# LED_Matrix_3_1.net
KiCad netlist of a schematic drawn in EAGLE
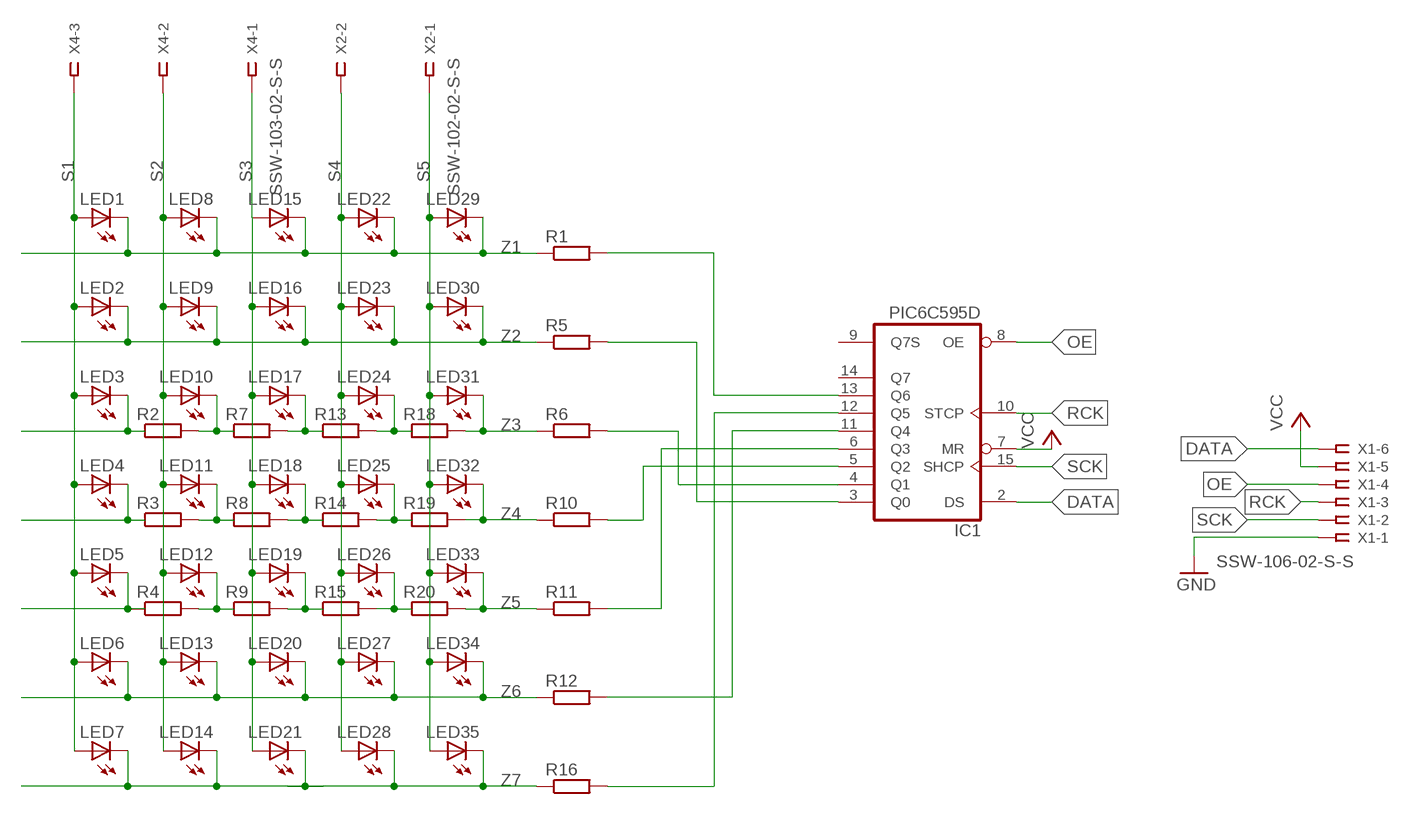
[diagram p0: schematic, sheet 1]

(export (version "E")
  (design (tool "Eeschema 10.0.6"))
  (components
    (comp (ref "IC1")
      (value "PIC6C595D")
      (footprint "eagle-import:SO16")
      (libsource (lib "eagle-import") (part "PIC6C595D"))
    )
    (comp (ref "LED1")
      (value "LEDCHIP-LED0603")
      (footprint "eagle-import:CHIP-LED0603")
      (libsource (lib "eagle-import") (part "LEDCHIP-LED0603"))
    )
    (comp (ref "LED2")
      (value "LEDCHIP-LED0603")
      (footprint "eagle-import:CHIP-LED0603")
      (libsource (lib "eagle-import") (part "LEDCHIP-LED0603"))
    )
    (comp (ref "LED3")
      (value "LEDCHIP-LED0603")
      (footprint "eagle-import:CHIP-LED0603")
      (libsource (lib "eagle-import") (part "LEDCHIP-LED0603"))
    )
    (comp (ref "LED4")
      (value "LEDCHIP-LED0603")
      (footprint "eagle-import:CHIP-LED0603")
      (libsource (lib "eagle-import") (part "LEDCHIP-LED0603"))
    )
    (comp (ref "LED5")
      (value "LEDCHIP-LED0603")
      (footprint "eagle-import:CHIP-LED0603")
      (libsource (lib "eagle-import") (part "LEDCHIP-LED0603"))
    )
    (comp (ref "LED6")
      (value "LEDCHIP-LED0603")
      (footprint "eagle-import:CHIP-LED0603")
      (libsource (lib "eagle-import") (part "LEDCHIP-LED0603"))
    )
    (comp (ref "LED7")
      (value "LEDCHIP-LED0603")
      (footprint "eagle-import:CHIP-LED0603")
      (libsource (lib "eagle-import") (part "LEDCHIP-LED0603"))
    )
    (comp (ref "LED8")
      (value "LEDCHIP-LED0603")
      (footprint "eagle-import:CHIP-LED0603")
      (libsource (lib "eagle-import") (part "LEDCHIP-LED0603"))
    )
    (comp (ref "LED9")
      (value "LEDCHIP-LED0603")
      (footprint "eagle-import:CHIP-LED0603")
      (libsource (lib "eagle-import") (part "LEDCHIP-LED0603"))
    )
    (comp (ref "LED10")
      (value "LEDCHIP-LED0603")
      (footprint "eagle-import:CHIP-LED0603")
      (libsource (lib "eagle-import") (part "LEDCHIP-LED0603"))
    )
    (comp (ref "LED11")
      (value "LEDCHIP-LED0603")
      (footprint "eagle-import:CHIP-LED0603")
      (libsource (lib "eagle-import") (part "LEDCHIP-LED0603"))
    )
    (comp (ref "LED12")
      (value "LEDCHIP-LED0603")
      (footprint "eagle-import:CHIP-LED0603")
      (libsource (lib "eagle-import") (part "LEDCHIP-LED0603"))
    )
    (comp (ref "LED13")
      (value "LEDCHIP-LED0603")
      (footprint "eagle-import:CHIP-LED0603")
      (libsource (lib "eagle-import") (part "LEDCHIP-LED0603"))
    )
    (comp (ref "LED14")
      (value "LEDCHIP-LED0603")
      (footprint "eagle-import:CHIP-LED0603")
      (libsource (lib "eagle-import") (part "LEDCHIP-LED0603"))
    )
    (comp (ref "LED15")
      (value "LEDCHIP-LED0603")
      (footprint "eagle-import:CHIP-LED0603")
      (libsource (lib "eagle-import") (part "LEDCHIP-LED0603"))
    )
    (comp (ref "LED16")
      (value "LEDCHIP-LED0603")
      (footprint "eagle-import:CHIP-LED0603")
      (libsource (lib "eagle-import") (part "LEDCHIP-LED0603"))
    )
    (comp (ref "LED17")
      (value "LEDCHIP-LED0603")
      (footprint "eagle-import:CHIP-LED0603")
      (libsource (lib "eagle-import") (part "LEDCHIP-LED0603"))
    )
    (comp (ref "LED18")
      (value "LEDCHIP-LED0603")
      (footprint "eagle-import:CHIP-LED0603")
      (libsource (lib "eagle-import") (part "LEDCHIP-LED0603"))
    )
    (comp (ref "LED19")
      (value "LEDCHIP-LED0603")
      (footprint "eagle-import:CHIP-LED0603")
      (libsource (lib "eagle-import") (part "LEDCHIP-LED0603"))
    )
    (comp (ref "LED20")
      (value "LEDCHIP-LED0603")
      (footprint "eagle-import:CHIP-LED0603")
      (libsource (lib "eagle-import") (part "LEDCHIP-LED0603"))
    )
    (comp (ref "LED21")
      (value "LEDCHIP-LED0603")
      (footprint "eagle-import:CHIP-LED0603")
      (libsource (lib "eagle-import") (part "LEDCHIP-LED0603"))
    )
    (comp (ref "LED22")
      (value "LEDCHIP-LED0603")
      (footprint "eagle-import:CHIP-LED0603")
      (libsource (lib "eagle-import") (part "LEDCHIP-LED0603"))
    )
    (comp (ref "LED23")
      (value "LEDCHIP-LED0603")
      (footprint "eagle-import:CHIP-LED0603")
      (libsource (lib "eagle-import") (part "LEDCHIP-LED0603"))
    )
    (comp (ref "LED24")
      (value "LEDCHIP-LED0603")
      (footprint "eagle-import:CHIP-LED0603")
      (libsource (lib "eagle-import") (part "LEDCHIP-LED0603"))
    )
    (comp (ref "LED25")
      (value "LEDCHIP-LED0603")
      (footprint "eagle-import:CHIP-LED0603")
      (libsource (lib "eagle-import") (part "LEDCHIP-LED0603"))
    )
    (comp (ref "LED26")
      (value "LEDCHIP-LED0603")
      (footprint "eagle-import:CHIP-LED0603")
      (libsource (lib "eagle-import") (part "LEDCHIP-LED0603"))
    )
    (comp (ref "LED27")
      (value "LEDCHIP-LED0603")
      (footprint "eagle-import:CHIP-LED0603")
      (libsource (lib "eagle-import") (part "LEDCHIP-LED0603"))
    )
    (comp (ref "LED28")
      (value "LEDCHIP-LED0603")
      (footprint "eagle-import:CHIP-LED0603")
      (libsource (lib "eagle-import") (part "LEDCHIP-LED0603"))
    )
    (comp (ref "LED29")
      (value "LEDCHIP-LED0603")
      (footprint "eagle-import:CHIP-LED0603")
      (libsource (lib "eagle-import") (part "LEDCHIP-LED0603"))
    )
    (comp (ref "LED30")
      (value "LEDCHIP-LED0603")
      (footprint "eagle-import:CHIP-LED0603")
      (libsource (lib "eagle-import") (part "LEDCHIP-LED0603"))
    )
    (comp (ref "LED31")
      (value "LEDCHIP-LED0603")
      (footprint "eagle-import:CHIP-LED0603")
      (libsource (lib "eagle-import") (part "LEDCHIP-LED0603"))
    )
    (comp (ref "LED32")
      (value "LEDCHIP-LED0603")
      (footprint "eagle-import:CHIP-LED0603")
      (libsource (lib "eagle-import") (part "LEDCHIP-LED0603"))
    )
    (comp (ref "LED33")
      (value "LEDCHIP-LED0603")
      (footprint "eagle-import:CHIP-LED0603")
      (libsource (lib "eagle-import") (part "LEDCHIP-LED0603"))
    )
    (comp (ref "LED34")
      (value "LEDCHIP-LED0603")
      (footprint "eagle-import:CHIP-LED0603")
      (libsource (lib "eagle-import") (part "LEDCHIP-LED0603"))
    )
    (comp (ref "LED35")
      (value "LEDCHIP-LED0603")
      (footprint "eagle-import:CHIP-LED0603")
      (libsource (lib "eagle-import") (part "LEDCHIP-LED0603"))
    )
    (comp (ref "R1")
      (value "R-EU_R0603")
      (footprint "eagle-import:R0603")
      (libsource (lib "eagle-import") (part "resistor_R-EU_R0603"))
    )
    (comp (ref "R2")
      (value "R-EU_R0603")
      (footprint "eagle-import:R0603")
      (libsource (lib "eagle-import") (part "R-EU_R0603"))
    )
    (comp (ref "R3")
      (value "R-EU_R0603")
      (footprint "eagle-import:R0603")
      (libsource (lib "eagle-import") (part "R-EU_R0603"))
    )
    (comp (ref "R4")
      (value "R-EU_R0603")
      (footprint "eagle-import:R0603")
      (libsource (lib "eagle-import") (part "R-EU_R0603"))
    )
    (comp (ref "R5")
      (value "R-EU_R0603")
      (footprint "eagle-import:R0603")
      (libsource (lib "eagle-import") (part "resistor_R-EU_R0603"))
    )
    (comp (ref "R6")
      (value "R-EU_R0603")
      (footprint "eagle-import:R0603")
      (libsource (lib "eagle-import") (part "resistor_R-EU_R0603"))
    )
    (comp (ref "R7")
      (value "R-EU_R0603")
      (footprint "eagle-import:R0603")
      (libsource (lib "eagle-import") (part "R-EU_R0603"))
    )
    (comp (ref "R8")
      (value "R-EU_R0603")
      (footprint "eagle-import:R0603")
      (libsource (lib "eagle-import") (part "R-EU_R0603"))
    )
    (comp (ref "R9")
      (value "R-EU_R0603")
      (footprint "eagle-import:R0603")
      (libsource (lib "eagle-import") (part "R-EU_R0603"))
    )
    (comp (ref "R10")
      (value "R-EU_R0603")
      (footprint "eagle-import:R0603")
      (libsource (lib "eagle-import") (part "resistor_R-EU_R0603"))
    )
    (comp (ref "R11")
      (value "R-EU_R0603")
      (footprint "eagle-import:R0603")
      (libsource (lib "eagle-import") (part "resistor_R-EU_R0603"))
    )
    (comp (ref "R12")
      (value "R-EU_R0603")
      (footprint "eagle-import:R0603")
      (libsource (lib "eagle-import") (part "resistor_R-EU_R0603"))
    )
    (comp (ref "R13")
      (value "R-EU_R0603")
      (footprint "eagle-import:R0603")
      (libsource (lib "eagle-import") (part "R-EU_R0603"))
    )
    (comp (ref "R14")
      (value "R-EU_R0603")
      (footprint "eagle-import:R0603")
      (libsource (lib "eagle-import") (part "R-EU_R0603"))
    )
    (comp (ref "R15")
      (value "R-EU_R0603")
      (footprint "eagle-import:R0603")
      (libsource (lib "eagle-import") (part "R-EU_R0603"))
    )
    (comp (ref "R16")
      (value "R-EU_R0603")
      (footprint "eagle-import:R0603")
      (libsource (lib "eagle-import") (part "resistor_R-EU_R0603"))
    )
    (comp (ref "R18")
      (value "R-EU_R0603")
      (footprint "eagle-import:R0603")
      (libsource (lib "eagle-import") (part "R-EU_R0603"))
    )
    (comp (ref "R19")
      (value "R-EU_R0603")
      (footprint "eagle-import:R0603")
      (libsource (lib "eagle-import") (part "R-EU_R0603"))
    )
    (comp (ref "R20")
      (value "R-EU_R0603")
      (footprint "eagle-import:R0603")
      (libsource (lib "eagle-import") (part "R-EU_R0603"))
    )
    (comp (ref "X1")
      (value "SSW-106-02-S-S")
      (footprint "eagle-import:SSW-106-02-S-S")
      (libsource (lib "eagle-import") (part "SSW-106-02-S-S"))
    )
    (comp (ref "X2")
      (value "SSW-102-02-S-S")
      (footprint "eagle-import:SSW-102-02-S-S")
      (libsource (lib "eagle-import") (part "SSW-102-02-S-S"))
    )
    (comp (ref "X4")
      (value "SSW-103-02-S-S")
      (footprint "eagle-import:SSW-103-02-S-S")
      (libsource (lib "eagle-import") (part "SSW-103-02-S-S"))
    )
  )
  (nets
    (net (code "1") (name "/S1") (class "Default")
      (node (ref "LED1") (pin "A") (pinfunction "A_A") (pintype "passive"))
      (node (ref "LED2") (pin "A") (pinfunction "A_A") (pintype "passive"))
      (node (ref "LED3") (pin "A") (pinfunction "A_A") (pintype "passive"))
      (node (ref "LED4") (pin "A") (pinfunction "A_A") (pintype "passive"))
      (node (ref "LED5") (pin "A") (pinfunction "A_A") (pintype "passive"))
      (node (ref "LED6") (pin "A") (pinfunction "A_A") (pintype "passive"))
      (node (ref "LED7") (pin "A") (pinfunction "A_A") (pintype "passive"))
      (node (ref "X4") (pin "3") (pinfunction "1_3") (pintype "passive"))
    )
    (net (code "2") (name "/S2") (class "Default")
      (node (ref "LED10") (pin "A") (pinfunction "A_A") (pintype "passive"))
      (node (ref "LED11") (pin "A") (pinfunction "A_A") (pintype "passive"))
      (node (ref "LED12") (pin "A") (pinfunction "A_A") (pintype "passive"))
      (node (ref "LED13") (pin "A") (pinfunction "A_A") (pintype "passive"))
      (node (ref "LED14") (pin "A") (pinfunction "A_A") (pintype "passive"))
      (node (ref "LED8") (pin "A") (pinfunction "A_A") (pintype "passive"))
      (node (ref "LED9") (pin "A") (pinfunction "A_A") (pintype "passive"))
      (node (ref "X4") (pin "2") (pinfunction "1_2") (pintype "passive"))
    )
    (net (code "3") (name "/S3") (class "Default")
      (node (ref "LED15") (pin "A") (pinfunction "A_A") (pintype "passive"))
      (node (ref "LED16") (pin "A") (pinfunction "A_A") (pintype "passive"))
      (node (ref "LED17") (pin "A") (pinfunction "A_A") (pintype "passive"))
      (node (ref "LED18") (pin "A") (pinfunction "A_A") (pintype "passive"))
      (node (ref "LED19") (pin "A") (pinfunction "A_A") (pintype "passive"))
      (node (ref "LED20") (pin "A") (pinfunction "A_A") (pintype "passive"))
      (node (ref "LED21") (pin "A") (pinfunction "A_A") (pintype "passive"))
      (node (ref "X4") (pin "1") (pinfunction "1_1") (pintype "passive"))
    )
    (net (code "4") (name "/S4") (class "Default")
      (node (ref "LED22") (pin "A") (pinfunction "A_A") (pintype "passive"))
      (node (ref "LED23") (pin "A") (pinfunction "A_A") (pintype "passive"))
      (node (ref "LED24") (pin "A") (pinfunction "A_A") (pintype "passive"))
      (node (ref "LED25") (pin "A") (pinfunction "A_A") (pintype "passive"))
      (node (ref "LED26") (pin "A") (pinfunction "A_A") (pintype "passive"))
      (node (ref "LED27") (pin "A") (pinfunction "A_A") (pintype "passive"))
      (node (ref "LED28") (pin "A") (pinfunction "A_A") (pintype "passive"))
      (node (ref "X2") (pin "2") (pinfunction "1_2") (pintype "passive"))
    )
    (net (code "5") (name "/S5") (class "Default")
      (node (ref "LED29") (pin "A") (pinfunction "A_A") (pintype "passive"))
      (node (ref "LED30") (pin "A") (pinfunction "A_A") (pintype "passive"))
      (node (ref "LED31") (pin "A") (pinfunction "A_A") (pintype "passive"))
      (node (ref "LED32") (pin "A") (pinfunction "A_A") (pintype "passive"))
      (node (ref "LED33") (pin "A") (pinfunction "A_A") (pintype "passive"))
      (node (ref "LED34") (pin "A") (pinfunction "A_A") (pintype "passive"))
      (node (ref "LED35") (pin "A") (pinfunction "A_A") (pintype "passive"))
      (node (ref "X2") (pin "1") (pinfunction "1_1") (pintype "passive"))
    )
    (net (code "6") (name "/Z1") (class "Default")
      (node (ref "LED1") (pin "C") (pinfunction "C_C") (pintype "passive"))
      (node (ref "LED15") (pin "C") (pinfunction "C_C") (pintype "passive"))
      (node (ref "LED22") (pin "C") (pinfunction "C_C") (pintype "passive"))
      (node (ref "LED29") (pin "C") (pinfunction "C_C") (pintype "passive"))
      (node (ref "LED8") (pin "C") (pinfunction "C_C") (pintype "passive"))
      (node (ref "R1") (pin "1") (pinfunction "1_1") (pintype "passive"))
    )
    (net (code "7") (name "/Z2") (class "Default")
      (node (ref "LED16") (pin "C") (pinfunction "C_C") (pintype "passive"))
      (node (ref "LED2") (pin "C") (pinfunction "C_C") (pintype "passive"))
      (node (ref "LED23") (pin "C") (pinfunction "C_C") (pintype "passive"))
      (node (ref "LED30") (pin "C") (pinfunction "C_C") (pintype "passive"))
      (node (ref "LED9") (pin "C") (pinfunction "C_C") (pintype "passive"))
      (node (ref "R5") (pin "1") (pinfunction "1_1") (pintype "passive"))
    )
    (net (code "8") (name "/Z3") (class "Default")
      (node (ref "LED31") (pin "C") (pinfunction "C_C") (pintype "passive"))
      (node (ref "R18") (pin "2") (pinfunction "2_2") (pintype "passive"))
      (node (ref "R6") (pin "1") (pinfunction "1_1") (pintype "passive"))
    )
    (net (code "9") (name "/Z4") (class "Default")
      (node (ref "LED32") (pin "C") (pinfunction "C_C") (pintype "passive"))
      (node (ref "R10") (pin "1") (pinfunction "1_1") (pintype "passive"))
      (node (ref "R19") (pin "2") (pinfunction "2_2") (pintype "passive"))
    )
    (net (code "10") (name "/Z5") (class "Default")
      (node (ref "LED33") (pin "C") (pinfunction "C_C") (pintype "passive"))
      (node (ref "R11") (pin "1") (pinfunction "1_1") (pintype "passive"))
      (node (ref "R20") (pin "2") (pinfunction "2_2") (pintype "passive"))
    )
    (net (code "11") (name "/Z6") (class "Default")
      (node (ref "LED13") (pin "C") (pinfunction "C_C") (pintype "passive"))
      (node (ref "LED20") (pin "C") (pinfunction "C_C") (pintype "passive"))
      (node (ref "LED27") (pin "C") (pinfunction "C_C") (pintype "passive"))
      (node (ref "LED34") (pin "C") (pinfunction "C_C") (pintype "passive"))
      (node (ref "LED6") (pin "C") (pinfunction "C_C") (pintype "passive"))
      (node (ref "R12") (pin "1") (pinfunction "1_1") (pintype "passive"))
    )
    (net (code "12") (name "/Z7") (class "Default")
      (node (ref "LED14") (pin "C") (pinfunction "C_C") (pintype "passive"))
      (node (ref "LED21") (pin "C") (pinfunction "C_C") (pintype "passive"))
      (node (ref "LED28") (pin "C") (pinfunction "C_C") (pintype "passive"))
      (node (ref "LED35") (pin "C") (pinfunction "C_C") (pintype "passive"))
      (node (ref "LED7") (pin "C") (pinfunction "C_C") (pintype "passive"))
      (node (ref "R16") (pin "1") (pinfunction "1_1") (pintype "passive"))
    )
    (net (code "13") (name "DATA") (class "Default")
      (node (ref "IC1") (pin "2") (pinfunction "DS_2") (pintype "input"))
      (node (ref "X1") (pin "6") (pinfunction "1_6") (pintype "passive"))
    )
    (net (code "14") (name "GND") (class "Default")
      (node (ref "X1") (pin "1") (pinfunction "1_1") (pintype "passive"))
    )
    (net (code "15") (name "Net-(IC1A-Q0)") (class "Default")
      (node (ref "IC1") (pin "3") (pinfunction "Q0_3") (pintype "tri_state"))
      (node (ref "R5") (pin "2") (pinfunction "2_2") (pintype "passive"))
    )
    (net (code "16") (name "Net-(IC1A-Q1)") (class "Default")
      (node (ref "IC1") (pin "4") (pinfunction "Q1_4") (pintype "tri_state"))
      (node (ref "R6") (pin "2") (pinfunction "2_2") (pintype "passive"))
    )
    (net (code "17") (name "Net-(IC1A-Q2)") (class "Default")
      (node (ref "IC1") (pin "5") (pinfunction "Q2_5") (pintype "tri_state"))
      (node (ref "R10") (pin "2") (pinfunction "2_2") (pintype "passive"))
    )
    (net (code "18") (name "Net-(IC1A-Q3)") (class "Default")
      (node (ref "IC1") (pin "6") (pinfunction "Q3_6") (pintype "tri_state"))
      (node (ref "R11") (pin "2") (pinfunction "2_2") (pintype "passive"))
    )
    (net (code "19") (name "Net-(IC1A-Q4)") (class "Default")
      (node (ref "IC1") (pin "11") (pinfunction "Q4_11") (pintype "tri_state"))
      (node (ref "R12") (pin "2") (pinfunction "2_2") (pintype "passive"))
    )
    (net (code "20") (name "Net-(IC1A-Q5)") (class "Default")
      (node (ref "IC1") (pin "12") (pinfunction "Q5_12") (pintype "tri_state"))
      (node (ref "R16") (pin "2") (pinfunction "2_2") (pintype "passive"))
    )
    (net (code "21") (name "Net-(IC1A-Q6)") (class "Default")
      (node (ref "IC1") (pin "13") (pinfunction "Q6_13") (pintype "tri_state"))
      (node (ref "R1") (pin "2") (pinfunction "2_2") (pintype "passive"))
    )
    (net (code "22") (name "Net-(LED3-PadC)") (class "Default")
      (node (ref "LED3") (pin "C") (pinfunction "C_C") (pintype "passive"))
      (node (ref "R2") (pin "1") (pinfunction "1_1") (pintype "passive"))
    )
    (net (code "23") (name "Net-(LED4-PadC)") (class "Default")
      (node (ref "LED4") (pin "C") (pinfunction "C_C") (pintype "passive"))
      (node (ref "R3") (pin "1") (pinfunction "1_1") (pintype "passive"))
    )
    (net (code "24") (name "Net-(LED5-PadC)") (class "Default")
      (node (ref "LED5") (pin "C") (pinfunction "C_C") (pintype "passive"))
      (node (ref "R4") (pin "1") (pinfunction "1_1") (pintype "passive"))
    )
    (net (code "25") (name "Net-(LED10-PadC)") (class "Default")
      (node (ref "LED10") (pin "C") (pinfunction "C_C") (pintype "passive"))
      (node (ref "R2") (pin "2") (pinfunction "2_2") (pintype "passive"))
      (node (ref "R7") (pin "1") (pinfunction "1_1") (pintype "passive"))
    )
    (net (code "26") (name "Net-(LED11-PadC)") (class "Default")
      (node (ref "LED11") (pin "C") (pinfunction "C_C") (pintype "passive"))
      (node (ref "R3") (pin "2") (pinfunction "2_2") (pintype "passive"))
      (node (ref "R8") (pin "1") (pinfunction "1_1") (pintype "passive"))
    )
    (net (code "27") (name "Net-(LED12-PadC)") (class "Default")
      (node (ref "LED12") (pin "C") (pinfunction "C_C") (pintype "passive"))
      (node (ref "R4") (pin "2") (pinfunction "2_2") (pintype "passive"))
      (node (ref "R9") (pin "1") (pinfunction "1_1") (pintype "passive"))
    )
    (net (code "28") (name "Net-(LED17-PadC)") (class "Default")
      (node (ref "LED17") (pin "C") (pinfunction "C_C") (pintype "passive"))
      (node (ref "R13") (pin "1") (pinfunction "1_1") (pintype "passive"))
      (node (ref "R7") (pin "2") (pinfunction "2_2") (pintype "passive"))
    )
    (net (code "29") (name "Net-(LED18-PadC)") (class "Default")
      (node (ref "LED18") (pin "C") (pinfunction "C_C") (pintype "passive"))
      (node (ref "R14") (pin "1") (pinfunction "1_1") (pintype "passive"))
      (node (ref "R8") (pin "2") (pinfunction "2_2") (pintype "passive"))
    )
    (net (code "30") (name "Net-(LED19-PadC)") (class "Default")
      (node (ref "LED19") (pin "C") (pinfunction "C_C") (pintype "passive"))
      (node (ref "R15") (pin "1") (pinfunction "1_1") (pintype "passive"))
      (node (ref "R9") (pin "2") (pinfunction "2_2") (pintype "passive"))
    )
    (net (code "31") (name "Net-(LED24-PadC)") (class "Default")
      (node (ref "LED24") (pin "C") (pinfunction "C_C") (pintype "passive"))
      (node (ref "R13") (pin "2") (pinfunction "2_2") (pintype "passive"))
      (node (ref "R18") (pin "1") (pinfunction "1_1") (pintype "passive"))
    )
    (net (code "32") (name "Net-(LED25-PadC)") (class "Default")
      (node (ref "LED25") (pin "C") (pinfunction "C_C") (pintype "passive"))
      (node (ref "R14") (pin "2") (pinfunction "2_2") (pintype "passive"))
      (node (ref "R19") (pin "1") (pinfunction "1_1") (pintype "passive"))
    )
    (net (code "33") (name "Net-(LED26-PadC)") (class "Default")
      (node (ref "LED26") (pin "C") (pinfunction "C_C") (pintype "passive"))
      (node (ref "R15") (pin "2") (pinfunction "2_2") (pintype "passive"))
      (node (ref "R20") (pin "1") (pinfunction "1_1") (pintype "passive"))
    )
    (net (code "34") (name "OE") (class "Default")
      (node (ref "IC1") (pin "8") (pinfunction "OE_8") (pintype "input"))
      (node (ref "X1") (pin "4") (pinfunction "1_4") (pintype "passive"))
    )
    (net (code "35") (name "RCK") (class "Default")
      (node (ref "IC1") (pin "10") (pinfunction "STCP_10") (pintype "input"))
      (node (ref "X1") (pin "3") (pinfunction "1_3") (pintype "passive"))
    )
    (net (code "36") (name "SCK") (class "Default")
      (node (ref "IC1") (pin "15") (pinfunction "SHCP_15") (pintype "input"))
      (node (ref "X1") (pin "2") (pinfunction "1_2") (pintype "passive"))
    )
    (net (code "37") (name "VCC") (class "Default")
      (node (ref "IC1") (pin "7") (pinfunction "MR_7") (pintype "input"))
      (node (ref "X1") (pin "5") (pinfunction "1_5") (pintype "passive"))
    )
    (net (code "38") (name "unconnected-(IC1A-Q7-Pad14)") (class "Default")
      (node (ref "IC1") (pin "14") (pinfunction "Q7_14") (pintype "tri_state"))
    )
    (net (code "39") (name "unconnected-(IC1A-Q7S-Pad9)") (class "Default")
      (node (ref "IC1") (pin "9") (pinfunction "Q7S_9") (pintype "tri_state"))
    )
  )
)
